# ESP_PIC_v1.net
KiCad netlist of a schematic drawn in Altium Designer
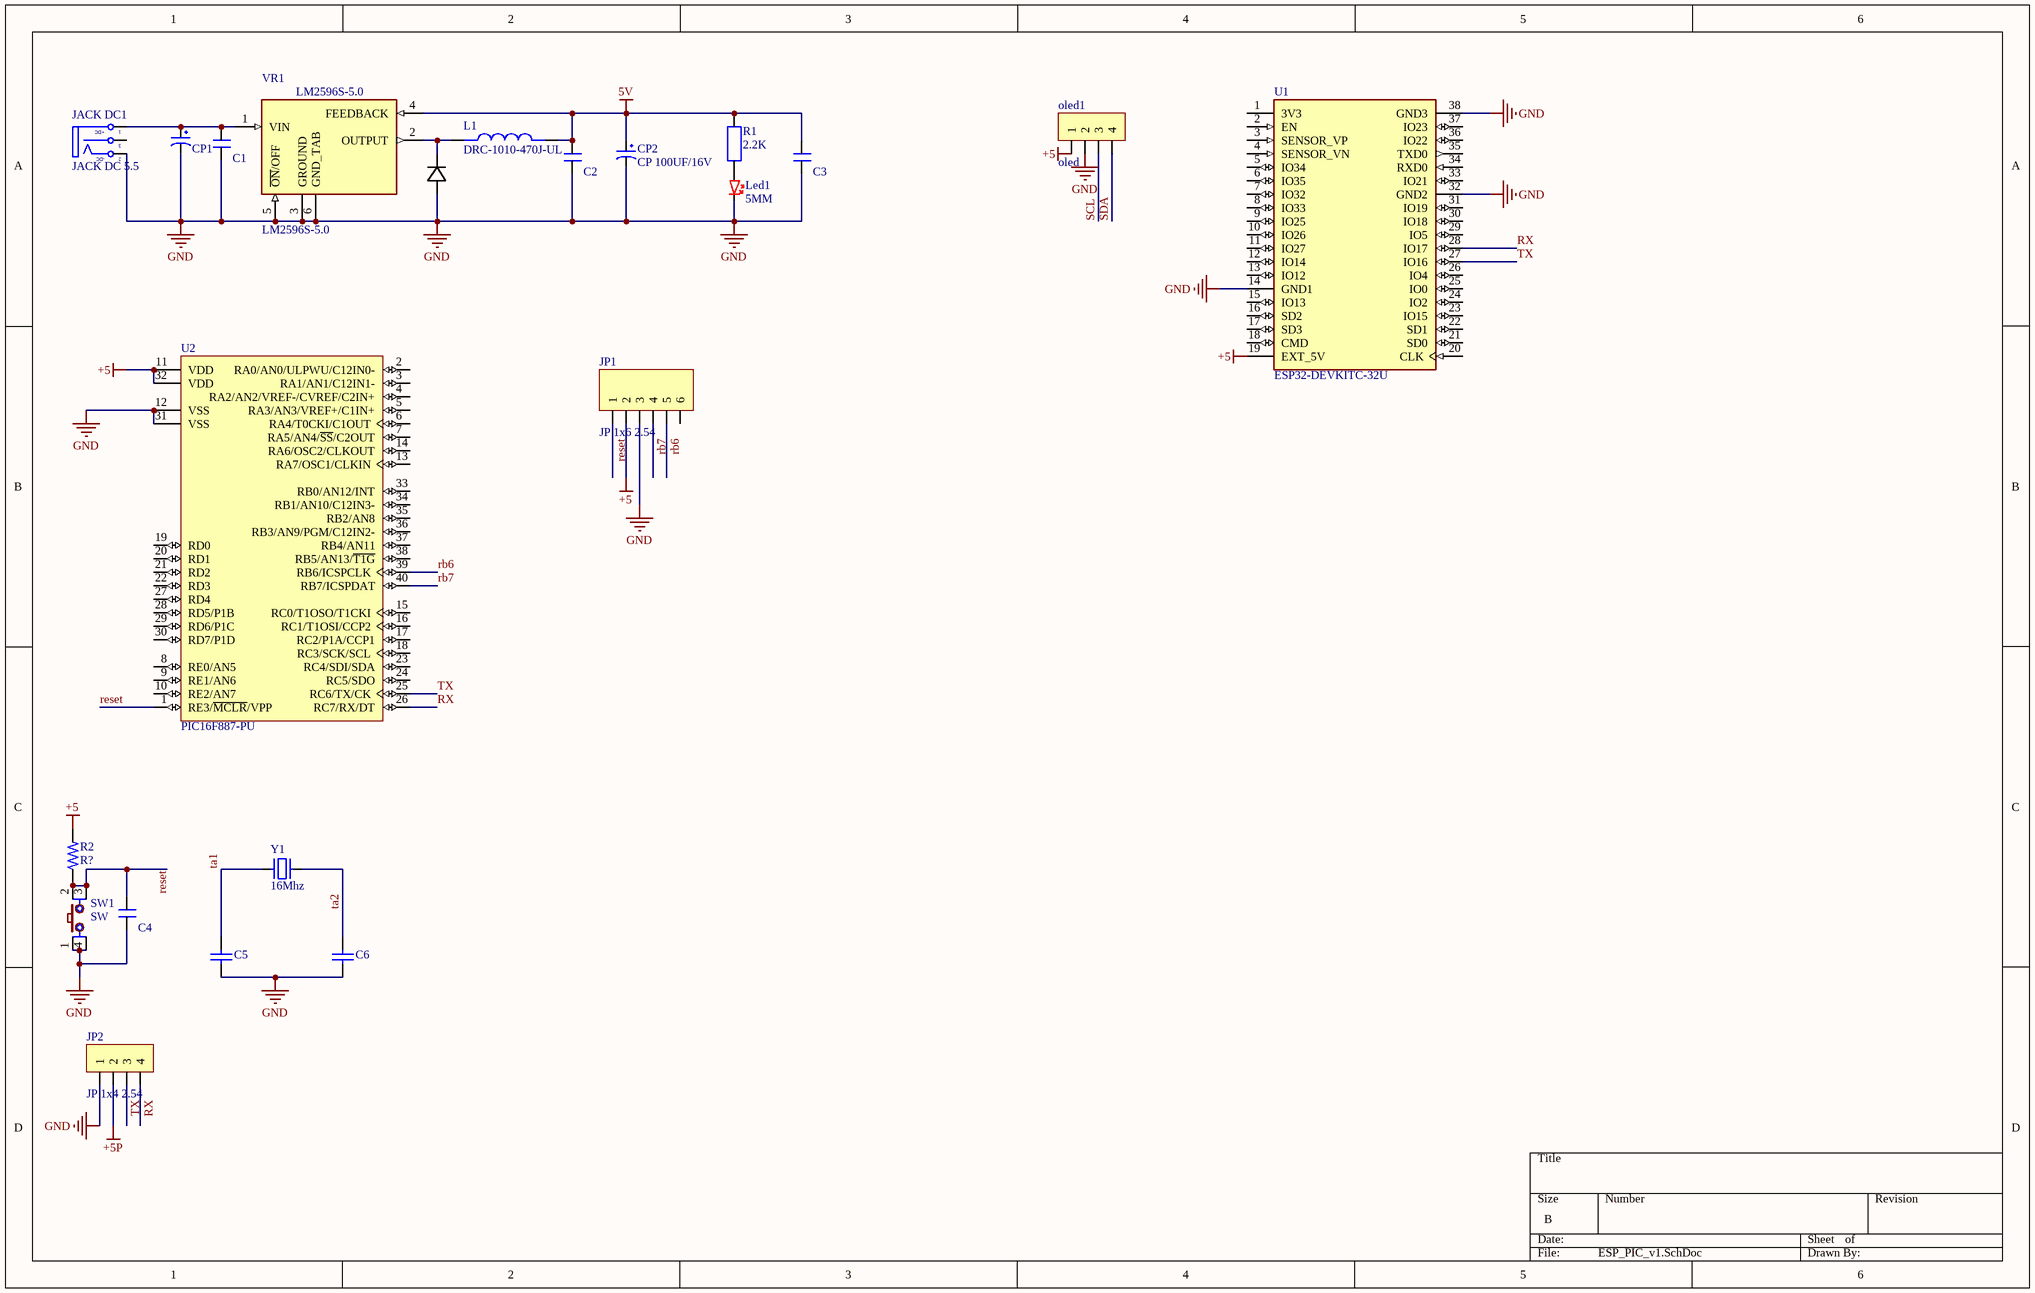
[diagram p0: ESP_PIC_v1.SchDoc]

(export (version "E")
  (design (tool "Eeschema 10.0.6"))
  (components
    (comp (ref "C1")
      (value "C")
      (footprint "Tu gom")
      (description "2.54MM -DIP")
      (libsource (lib "PLG_RC") (part "TỤ GỐM"))
    )
    (comp (ref "C2")
      (value "C")
      (footprint "Tu gom")
      (description "2.54MM -DIP")
      (libsource (lib "PLG_RC") (part "TỤ GỐM"))
    )
    (comp (ref "C3")
      (value "C")
      (footprint "Tu gom")
      (description "2.54MM -DIP")
      (libsource (lib "PLG_RC") (part "TỤ GỐM"))
    )
    (comp (ref "C4")
      (value "C")
      (footprint "Tu gom")
      (description "2.54MM -DIP")
      (libsource (lib "PLG_RC") (part "TỤ GỐM"))
    )
    (comp (ref "C5")
      (value "Capacitor Ceramic")
      (footprint "C0805")
      (description "Capacitor")
      (fields (field (name "PUBLISHER") "Altium Limited"))
      (libsource (lib "Cty1") (part "CapSMD"))
    )
    (comp (ref "C6")
      (value "Capacitor Ceramic")
      (footprint "C0805")
      (description "Capacitor")
      (fields (field (name "PUBLISHER") "Altium Limited"))
      (libsource (lib "Cty1") (part "CapSMD"))
    )
    (comp (ref "CP1")
      (value "CP?")
      (footprint "C10mm")
      (description "CP 1000UF/35V")
      (libsource (lib "PLG_RC") (part "CP 1000UF/35V"))
    )
    (comp (ref "CP2")
      (value "CP 100UF/16V")
      (footprint "C5mm")
      (description "CP?")
      (libsource (lib "LeQuangDinh") (part "CP 100UF/16V"))
    )
    (comp (ref "Diode 1N4007")
      (value "Diode 1N4007")
      (footprint "Diode 1N4007")
      (description "Diode 1N4007 DIP")
      (libsource (lib "PLG_RC") (part "Diode 1N4007"))
    )
    (comp (ref "JACK DC1")
      (value "JACK DC 5.5")
      (footprint "JACK DC 5.5")
      (libsource (lib "PLG_RC") (part "JACK DC 5.5"))
    )
    (comp (ref "JP1")
      (value "JP 1x6 2.54")
      (footprint "JP 1x6 DT")
      (description "Cắm")
      (libsource (lib "LeQuangDinh1") (part "JP 1x6 2.54 Duc Thang"))
    )
    (comp (ref "JP2")
      (value "JP 1x4 2.54")
      (footprint "JP 1x4 DT")
      (description "Cắm")
      (libsource (lib "LeQuangDinh1") (part "JP 1x4 2.54 Duc Thang"))
    )
    (comp (ref "L1")
      (value "DRC-1010-470J-UL")
      (footprint "IND_DRC-1010-470J-UL")
      (fields (field (name "MF") "{'manufacturer': u'Signal Transformer'}"))
      (libsource (lib "SnapEDA_Library") (part "DRC-1010-470J-UL"))
    )
    (comp (ref "Led1") (value "5MM") (footprint "Led 5mm") (libsource (lib "PLG_RC") (part "LED RED 5MM")))
    (comp (ref "oled1")
      (value "oled")
      (footprint "oled 0.96")
      (description "Cắm")
      (libsource (lib "libpgt") (part "oled 0.96"))
    )
    (comp (ref "R1")
      (value "2.2K")
      (footprint "Resistor 1/4W")
      (description "DIP")
      (libsource (lib "PLG_RC") (part "RESISTOR  1/4W 2.2K"))
    )
    (comp (ref "R2")
      (value "R?")
      (footprint "RES 0805")
      (description "RES 0.36 OHM 1% 1/4W 0805")
      (fields (field (name "MF") "TE Connectivity") (field (name "MP") "2-2176053-1"))
      (libsource (lib "LeQuangDinh1") (part "RES 0805 SMD"))
    )
    (comp (ref "SW1")
      (value "SW")
      (footprint "SW2-DIP")
      (description "Switch button 4 pin")
      (libsource (lib "PLG_RC") (part "SW4"))
    )
    (comp (ref "U1")
      (value "ESP32-DEVKITC-32U")
      (footprint "MODULE_ESP32-DEVKITC-32U")
      (description "ESP32-DEVKITC")
      (libsource (lib "PLG_RC") (part "ESP32-DEVKITC-32U"))
    )
    (comp (ref "U2")
      (value "PIC16F887-PU")
      (footprint "DIP40")
      (fields (field (name "PUBLISHER") "Altium Limited"))
      (libsource (lib "PLG_RC") (part "PIC16F887-PU"))
    )
    (comp (ref "VR1")
      (value "LM2596S-5.0")
      (footprint "TO 263 - 5")
      (description "SIMPLE SWITCHER&reg; 4.5V to 40V, 3A Low Component Count Step-Down Regulator")
      (fields (field (name "MP") "LM2596S-5.0/NOPB") (field (name "MF") "Texas Instruments"))
      (libsource (lib "PLG_RC") (part "LM2596S-5.0"))
    )
    (comp (ref "Y1")
      (value "16Mhz")
      (footprint "Thach Anh 2 chan cam")
      (description "Crystal For all Crystal 2pin.")
      (libsource (lib "LeQuangDinh1") (part "Thach Anh 2 chan Cam"))
    )
  )
  (nets
    (net (code "1") (name "+5") (class "Default")
      (node (ref "JP1") (pin "2") (pinfunction "2_2") (pintype "passive"))
      (node (ref "R2") (pin "2") (pinfunction "2_2") (pintype "passive"))
      (node (ref "U1") (pin "19") (pinfunction "EXT_5V_19") (pintype "power_in"))
      (node (ref "U2") (pin "11") (pinfunction "VDD_11") (pintype "power_in"))
      (node (ref "U2") (pin "32") (pinfunction "VDD_32") (pintype "power_in"))
      (node (ref "oled1") (pin "1") (pinfunction "1_1") (pintype "passive"))
    )
    (net (code "2") (name "+5P") (class "Default")
      (node (ref "JP2") (pin "2") (pinfunction "2_2") (pintype "passive"))
    )
    (net (code "3") (name "/RX") (class "Default")
      (node (ref "JP2") (pin "4") (pinfunction "4_4") (pintype "passive"))
      (node (ref "U1") (pin "28") (pinfunction "IO17_28") (pintype "bidirectional"))
      (node (ref "U2") (pin "26") (pinfunction "RC7/RX/DT_26") (pintype "bidirectional"))
    )
    (net (code "4") (name "/SCL") (class "Default")
      (node (ref "oled1") (pin "3") (pinfunction "3_3") (pintype "passive"))
    )
    (net (code "5") (name "/SDA") (class "Default")
      (node (ref "oled1") (pin "4") (pinfunction "4_4") (pintype "passive"))
    )
    (net (code "6") (name "/TX") (class "Default")
      (node (ref "JP2") (pin "3") (pinfunction "3_3") (pintype "passive"))
      (node (ref "U1") (pin "27") (pinfunction "IO16_27") (pintype "bidirectional"))
      (node (ref "U2") (pin "25") (pinfunction "RC6/TX/CK_25") (pintype "bidirectional"))
    )
    (net (code "7") (name "/rb6") (class "Default")
      (node (ref "JP1") (pin "5") (pinfunction "5_5") (pintype "passive"))
      (node (ref "U2") (pin "39") (pinfunction "RB6/ICSPCLK_39") (pintype "bidirectional"))
    )
    (net (code "8") (name "/rb7") (class "Default")
      (node (ref "JP1") (pin "4") (pinfunction "4_4") (pintype "passive"))
      (node (ref "U2") (pin "40") (pinfunction "RB7/ICSPDAT_40") (pintype "bidirectional"))
    )
    (net (code "9") (name "/reset") (class "Default")
      (node (ref "C4") (pin "2") (pinfunction "2_2") (pintype "passive"))
      (node (ref "JP1") (pin "1") (pinfunction "1_1") (pintype "passive"))
      (node (ref "R2") (pin "1") (pinfunction "1_1") (pintype "passive"))
      (node (ref "SW1") (pin "2") (pinfunction "2_2") (pintype "passive"))
      (node (ref "SW1") (pin "3") (pinfunction "3_3") (pintype "passive"))
      (node (ref "U2") (pin "1") (pinfunction "RE3/~{MCLR}/VPP_1") (pintype "bidirectional"))
    )
    (net (code "10") (name "/ta1") (class "Default")
      (node (ref "C5") (pin "2") (pinfunction "2_2") (pintype "passive"))
      (node (ref "Y1") (pin "2") (pinfunction "2_2") (pintype "passive"))
    )
    (net (code "11") (name "/ta2") (class "Default")
      (node (ref "C6") (pin "2") (pinfunction "2_2") (pintype "passive"))
      (node (ref "Y1") (pin "1") (pinfunction "1_1") (pintype "passive"))
    )
    (net (code "12") (name "5V") (class "Default")
      (node (ref "C2") (pin "2") (pinfunction "2_2") (pintype "passive"))
      (node (ref "C3") (pin "2") (pinfunction "2_2") (pintype "passive"))
      (node (ref "CP2") (pin "1") (pinfunction "1_1") (pintype "passive"))
      (node (ref "L1") (pin "2") (pinfunction "2_2") (pintype "passive"))
      (node (ref "R1") (pin "2") (pinfunction "2_2") (pintype "passive"))
      (node (ref "VR1") (pin "4") (pinfunction "FEEDBACK_4") (pintype "input"))
    )
    (net (code "13") (name "GND") (class "Default")
      (node (ref "C1") (pin "1") (pinfunction "1_1") (pintype "passive"))
      (node (ref "C2") (pin "1") (pinfunction "1_1") (pintype "passive"))
      (node (ref "C3") (pin "1") (pinfunction "1_1") (pintype "passive"))
      (node (ref "C4") (pin "1") (pinfunction "1_1") (pintype "passive"))
      (node (ref "C5") (pin "1") (pinfunction "1_1") (pintype "passive"))
      (node (ref "C6") (pin "1") (pinfunction "1_1") (pintype "passive"))
      (node (ref "CP1") (pin "2") (pinfunction "2_2") (pintype "passive"))
      (node (ref "CP2") (pin "2") (pinfunction "2_2") (pintype "passive"))
      (node (ref "Diode 1N4007") (pin "1") (pinfunction "B_1") (pintype "passive"))
      (node (ref "JACK DC1") (pin "2") (pinfunction "TN_2") (pintype "passive"))
      (node (ref "JP1") (pin "3") (pinfunction "3_3") (pintype "passive"))
      (node (ref "JP2") (pin "1") (pinfunction "1_1") (pintype "passive"))
      (node (ref "Led1") (pin "2") (pinfunction "B_2") (pintype "passive"))
      (node (ref "SW1") (pin "1") (pintype "passive"))
      (node (ref "SW1") (pin "4") (pinfunction "4_4") (pintype "passive"))
      (node (ref "U1") (pin "14") (pinfunction "GND1_14") (pintype "power_in"))
      (node (ref "U1") (pin "32") (pinfunction "GND2_32") (pintype "power_in"))
      (node (ref "U1") (pin "38") (pinfunction "GND3_38") (pintype "power_in"))
      (node (ref "U2") (pin "12") (pinfunction "VSS_12") (pintype "power_in"))
      (node (ref "U2") (pin "31") (pinfunction "VSS_31") (pintype "power_in"))
      (node (ref "VR1") (pin "3") (pinfunction "GROUND_3") (pintype "power_in"))
      (node (ref "VR1") (pin "5") (pinfunction "~{ON}/OFF_5") (pintype "input"))
      (node (ref "VR1") (pin "6") (pinfunction "GND_TAB_6") (pintype "power_in"))
      (node (ref "oled1") (pin "2") (pinfunction "2_2") (pintype "passive"))
    )
    (net (code "14") (name "Net-(JACK DC1-T)") (class "Default")
      (node (ref "C1") (pin "2") (pinfunction "2_2") (pintype "passive"))
      (node (ref "CP1") (pin "1") (pinfunction "1_1") (pintype "passive"))
      (node (ref "JACK DC1") (pin "1") (pinfunction "T_1") (pintype "passive"))
      (node (ref "VR1") (pin "1") (pinfunction "VIN_1") (pintype "input"))
    )
    (net (code "15") (name "Net-(Led1-B-Pad1)") (class "Default")
      (node (ref "Led1") (pin "1") (pinfunction "B_1") (pintype "passive"))
      (node (ref "R1") (pin "1") (pinfunction "1_1") (pintype "passive"))
    )
    (net (code "16") (name "Net-(VR1-OUTPUT)") (class "Default")
      (node (ref "Diode 1N4007") (pin "2") (pinfunction "B_2") (pintype "passive"))
      (node (ref "L1") (pin "1") (pinfunction "1_1") (pintype "passive"))
      (node (ref "VR1") (pin "2") (pinfunction "OUTPUT_2") (pintype "output"))
    )
    (net (code "17") (name "unconnected-(JACK DC1-S-Pad3)") (class "Default")
      (node (ref "JACK DC1") (pin "3") (pinfunction "S_3") (pintype "power_in"))
    )
    (net (code "18") (name "unconnected-(JP1-Pad6)") (class "Default")
      (node (ref "JP1") (pin "6") (pinfunction "6_6") (pintype "passive"))
    )
    (net (code "19") (name "unconnected-(U1-3V3-Pad1)") (class "Default")
      (node (ref "U1") (pin "1") (pinfunction "3V3_1") (pintype "power_in"))
    )
    (net (code "20") (name "unconnected-(U1-CLK-Pad20)") (class "Default")
      (node (ref "U1") (pin "20") (pinfunction "CLK_20") (pintype "input"))
    )
    (net (code "21") (name "unconnected-(U1-CMD-Pad18)") (class "Default")
      (node (ref "U1") (pin "18") (pinfunction "CMD_18") (pintype "bidirectional"))
    )
    (net (code "22") (name "unconnected-(U1-EN-Pad2)") (class "Default")
      (node (ref "U1") (pin "2") (pinfunction "EN_2") (pintype "input"))
    )
    (net (code "23") (name "unconnected-(U1-IO0-Pad25)") (class "Default")
      (node (ref "U1") (pin "25") (pinfunction "IO0_25") (pintype "bidirectional"))
    )
    (net (code "24") (name "unconnected-(U1-IO2-Pad24)") (class "Default")
      (node (ref "U1") (pin "24") (pinfunction "IO2_24") (pintype "bidirectional"))
    )
    (net (code "25") (name "unconnected-(U1-IO4-Pad26)") (class "Default")
      (node (ref "U1") (pin "26") (pinfunction "IO4_26") (pintype "bidirectional"))
    )
    (net (code "26") (name "unconnected-(U1-IO5-Pad29)") (class "Default")
      (node (ref "U1") (pin "29") (pinfunction "IO5_29") (pintype "bidirectional"))
    )
    (net (code "27") (name "unconnected-(U1-IO12-Pad13)") (class "Default")
      (node (ref "U1") (pin "13") (pinfunction "IO12_13") (pintype "bidirectional"))
    )
    (net (code "28") (name "unconnected-(U1-IO13-Pad15)") (class "Default")
      (node (ref "U1") (pin "15") (pinfunction "IO13_15") (pintype "bidirectional"))
    )
    (net (code "29") (name "unconnected-(U1-IO14-Pad12)") (class "Default")
      (node (ref "U1") (pin "12") (pinfunction "IO14_12") (pintype "bidirectional"))
    )
    (net (code "30") (name "unconnected-(U1-IO15-Pad23)") (class "Default")
      (node (ref "U1") (pin "23") (pinfunction "IO15_23") (pintype "bidirectional"))
    )
    (net (code "31") (name "unconnected-(U1-IO18-Pad30)") (class "Default")
      (node (ref "U1") (pin "30") (pinfunction "IO18_30") (pintype "bidirectional"))
    )
    (net (code "32") (name "unconnected-(U1-IO19-Pad31)") (class "Default")
      (node (ref "U1") (pin "31") (pinfunction "IO19_31") (pintype "bidirectional"))
    )
    (net (code "33") (name "unconnected-(U1-IO21-Pad33)") (class "Default")
      (node (ref "U1") (pin "33") (pinfunction "IO21_33") (pintype "bidirectional"))
    )
    (net (code "34") (name "unconnected-(U1-IO22-Pad36)") (class "Default")
      (node (ref "U1") (pin "36") (pinfunction "IO22_36") (pintype "bidirectional"))
    )
    (net (code "35") (name "unconnected-(U1-IO23-Pad37)") (class "Default")
      (node (ref "U1") (pin "37") (pinfunction "IO23_37") (pintype "bidirectional"))
    )
    (net (code "36") (name "unconnected-(U1-IO25-Pad9)") (class "Default")
      (node (ref "U1") (pin "9") (pinfunction "IO25_9") (pintype "bidirectional"))
    )
    (net (code "37") (name "unconnected-(U1-IO26-Pad10)") (class "Default")
      (node (ref "U1") (pin "10") (pinfunction "IO26_10") (pintype "bidirectional"))
    )
    (net (code "38") (name "unconnected-(U1-IO27-Pad11)") (class "Default")
      (node (ref "U1") (pin "11") (pinfunction "IO27_11") (pintype "bidirectional"))
    )
    (net (code "39") (name "unconnected-(U1-IO32-Pad7)") (class "Default")
      (node (ref "U1") (pin "7") (pinfunction "IO32_7") (pintype "bidirectional"))
    )
    (net (code "40") (name "unconnected-(U1-IO33-Pad8)") (class "Default")
      (node (ref "U1") (pin "8") (pinfunction "IO33_8") (pintype "bidirectional"))
    )
    (net (code "41") (name "unconnected-(U1-IO34-Pad5)") (class "Default")
      (node (ref "U1") (pin "5") (pinfunction "IO34_5") (pintype "bidirectional"))
    )
    (net (code "42") (name "unconnected-(U1-IO35-Pad6)") (class "Default")
      (node (ref "U1") (pin "6") (pinfunction "IO35_6") (pintype "bidirectional"))
    )
    (net (code "43") (name "unconnected-(U1-RXD0-Pad34)") (class "Default")
      (node (ref "U1") (pin "34") (pinfunction "RXD0_34") (pintype "input"))
    )
    (net (code "44") (name "unconnected-(U1-SD0-Pad21)") (class "Default")
      (node (ref "U1") (pin "21") (pinfunction "SD0_21") (pintype "bidirectional"))
    )
    (net (code "45") (name "unconnected-(U1-SD1-Pad22)") (class "Default")
      (node (ref "U1") (pin "22") (pinfunction "SD1_22") (pintype "bidirectional"))
    )
    (net (code "46") (name "unconnected-(U1-SD2-Pad16)") (class "Default")
      (node (ref "U1") (pin "16") (pinfunction "SD2_16") (pintype "bidirectional"))
    )
    (net (code "47") (name "unconnected-(U1-SD3-Pad17)") (class "Default")
      (node (ref "U1") (pin "17") (pinfunction "SD3_17") (pintype "bidirectional"))
    )
    (net (code "48") (name "unconnected-(U1-SENSOR_VN-Pad4)") (class "Default")
      (node (ref "U1") (pin "4") (pinfunction "SENSOR_VN_4") (pintype "input"))
    )
    (net (code "49") (name "unconnected-(U1-SENSOR_VP-Pad3)") (class "Default")
      (node (ref "U1") (pin "3") (pinfunction "SENSOR_VP_3") (pintype "input"))
    )
    (net (code "50") (name "unconnected-(U1-TXD0-Pad35)") (class "Default")
      (node (ref "U1") (pin "35") (pinfunction "TXD0_35") (pintype "output"))
    )
    (net (code "51") (name "unconnected-(U2-RA0{slash}AN0{slash}ULPWU{slash}C12IN0--Pad2)") (class "Default")
      (node (ref "U2") (pin "2") (pinfunction "RA0/AN0/ULPWU/C12IN0-_2") (pintype "bidirectional"))
    )
    (net (code "52") (name "unconnected-(U2-RA1{slash}AN1{slash}C12IN1--Pad3)") (class "Default")
      (node (ref "U2") (pin "3") (pinfunction "RA1/AN1/C12IN1-_3") (pintype "bidirectional"))
    )
    (net (code "53") (name "unconnected-(U2-RA2{slash}AN2{slash}VREF-{slash}CVREF{slash}C2IN+-Pad4)") (class "Default")
      (node (ref "U2") (pin "4") (pinfunction "RA2/AN2/VREF-/CVREF/C2IN+_4") (pintype "bidirectional"))
    )
    (net (code "54") (name "unconnected-(U2-RA3{slash}AN3{slash}VREF+{slash}C1IN+-Pad5)") (class "Default")
      (node (ref "U2") (pin "5") (pinfunction "RA3/AN3/VREF+/C1IN+_5") (pintype "bidirectional"))
    )
    (net (code "55") (name "unconnected-(U2-RA4{slash}T0CKI{slash}C1OUT-Pad6)") (class "Default")
      (node (ref "U2") (pin "6") (pinfunction "RA4/T0CKI/C1OUT_6") (pintype "bidirectional"))
    )
    (net (code "56") (name "unconnected-(U2-RA5{slash}AN4{slash}~{SS}{slash}C2OUT-Pad7)") (class "Default")
      (node (ref "U2") (pin "7") (pinfunction "RA5/AN4/~{SS}/C2OUT_7") (pintype "bidirectional"))
    )
    (net (code "57") (name "unconnected-(U2-RA6{slash}OSC2{slash}CLKOUT-Pad14)") (class "Default")
      (node (ref "U2") (pin "14") (pinfunction "RA6/OSC2/CLKOUT_14") (pintype "bidirectional"))
    )
    (net (code "58") (name "unconnected-(U2-RA7{slash}OSC1{slash}CLKIN-Pad13)") (class "Default")
      (node (ref "U2") (pin "13") (pinfunction "RA7/OSC1/CLKIN_13") (pintype "bidirectional"))
    )
    (net (code "59") (name "unconnected-(U2-RB0{slash}AN12{slash}INT-Pad33)") (class "Default")
      (node (ref "U2") (pin "33") (pinfunction "RB0/AN12/INT_33") (pintype "bidirectional"))
    )
    (net (code "60") (name "unconnected-(U2-RB1{slash}AN10{slash}C12IN3--Pad34)") (class "Default")
      (node (ref "U2") (pin "34") (pinfunction "RB1/AN10/C12IN3-_34") (pintype "bidirectional"))
    )
    (net (code "61") (name "unconnected-(U2-RB2{slash}AN8-Pad35)") (class "Default")
      (node (ref "U2") (pin "35") (pinfunction "RB2/AN8_35") (pintype "bidirectional"))
    )
    (net (code "62") (name "unconnected-(U2-RB3{slash}AN9{slash}PGM{slash}C12IN2--Pad36)") (class "Default")
      (node (ref "U2") (pin "36") (pinfunction "RB3/AN9/PGM/C12IN2-_36") (pintype "bidirectional"))
    )
    (net (code "63") (name "unconnected-(U2-RB4{slash}AN11-Pad37)") (class "Default")
      (node (ref "U2") (pin "37") (pinfunction "RB4/AN11_37") (pintype "bidirectional"))
    )
    (net (code "64") (name "unconnected-(U2-RB5{slash}AN13{slash}~{T1G}-Pad38)") (class "Default")
      (node (ref "U2") (pin "38") (pinfunction "RB5/AN13/~{T1G}_38") (pintype "bidirectional"))
    )
    (net (code "65") (name "unconnected-(U2-RC0{slash}T1OSO{slash}T1CKI-Pad15)") (class "Default")
      (node (ref "U2") (pin "15") (pinfunction "RC0/T1OSO/T1CKI_15") (pintype "bidirectional"))
    )
    (net (code "66") (name "unconnected-(U2-RC1{slash}T1OSI{slash}CCP2-Pad16)") (class "Default")
      (node (ref "U2") (pin "16") (pinfunction "RC1/T1OSI/CCP2_16") (pintype "bidirectional"))
    )
    (net (code "67") (name "unconnected-(U2-RC2{slash}P1A{slash}CCP1-Pad17)") (class "Default")
      (node (ref "U2") (pin "17") (pinfunction "RC2/P1A/CCP1_17") (pintype "bidirectional"))
    )
    (net (code "68") (name "unconnected-(U2-RC3{slash}SCK{slash}SCL-Pad18)") (class "Default")
      (node (ref "U2") (pin "18") (pinfunction "RC3/SCK/SCL_18") (pintype "bidirectional"))
    )
    (net (code "69") (name "unconnected-(U2-RC4{slash}SDI{slash}SDA-Pad23)") (class "Default")
      (node (ref "U2") (pin "23") (pinfunction "RC4/SDI/SDA_23") (pintype "bidirectional"))
    )
    (net (code "70") (name "unconnected-(U2-RC5{slash}SDO-Pad24)") (class "Default")
      (node (ref "U2") (pin "24") (pinfunction "RC5/SDO_24") (pintype "bidirectional"))
    )
    (net (code "71") (name "unconnected-(U2-RD0-Pad19)") (class "Default")
      (node (ref "U2") (pin "19") (pinfunction "RD0_19") (pintype "bidirectional"))
    )
    (net (code "72") (name "unconnected-(U2-RD1-Pad20)") (class "Default")
      (node (ref "U2") (pin "20") (pinfunction "RD1_20") (pintype "bidirectional"))
    )
    (net (code "73") (name "unconnected-(U2-RD2-Pad21)") (class "Default")
      (node (ref "U2") (pin "21") (pinfunction "RD2_21") (pintype "bidirectional"))
    )
    (net (code "74") (name "unconnected-(U2-RD3-Pad22)") (class "Default")
      (node (ref "U2") (pin "22") (pinfunction "RD3_22") (pintype "bidirectional"))
    )
    (net (code "75") (name "unconnected-(U2-RD4-Pad27)") (class "Default")
      (node (ref "U2") (pin "27") (pinfunction "RD4_27") (pintype "bidirectional"))
    )
    (net (code "76") (name "unconnected-(U2-RD5{slash}P1B-Pad28)") (class "Default")
      (node (ref "U2") (pin "28") (pinfunction "RD5/P1B_28") (pintype "bidirectional"))
    )
    (net (code "77") (name "unconnected-(U2-RD6{slash}P1C-Pad29)") (class "Default")
      (node (ref "U2") (pin "29") (pinfunction "RD6/P1C_29") (pintype "bidirectional"))
    )
    (net (code "78") (name "unconnected-(U2-RD7{slash}P1D-Pad30)") (class "Default")
      (node (ref "U2") (pin "30") (pinfunction "RD7/P1D_30") (pintype "bidirectional"))
    )
    (net (code "79") (name "unconnected-(U2-RE0{slash}AN5-Pad8)") (class "Default")
      (node (ref "U2") (pin "8") (pinfunction "RE0/AN5_8") (pintype "bidirectional"))
    )
    (net (code "80") (name "unconnected-(U2-RE1{slash}AN6-Pad9)") (class "Default")
      (node (ref "U2") (pin "9") (pinfunction "RE1/AN6_9") (pintype "bidirectional"))
    )
    (net (code "81") (name "unconnected-(U2-RE2{slash}AN7-Pad10)") (class "Default")
      (node (ref "U2") (pin "10") (pinfunction "RE2/AN7_10") (pintype "bidirectional"))
    )
  )
)
